# board-v4.net
KiCad netlist of a schematic drawn in EAGLE
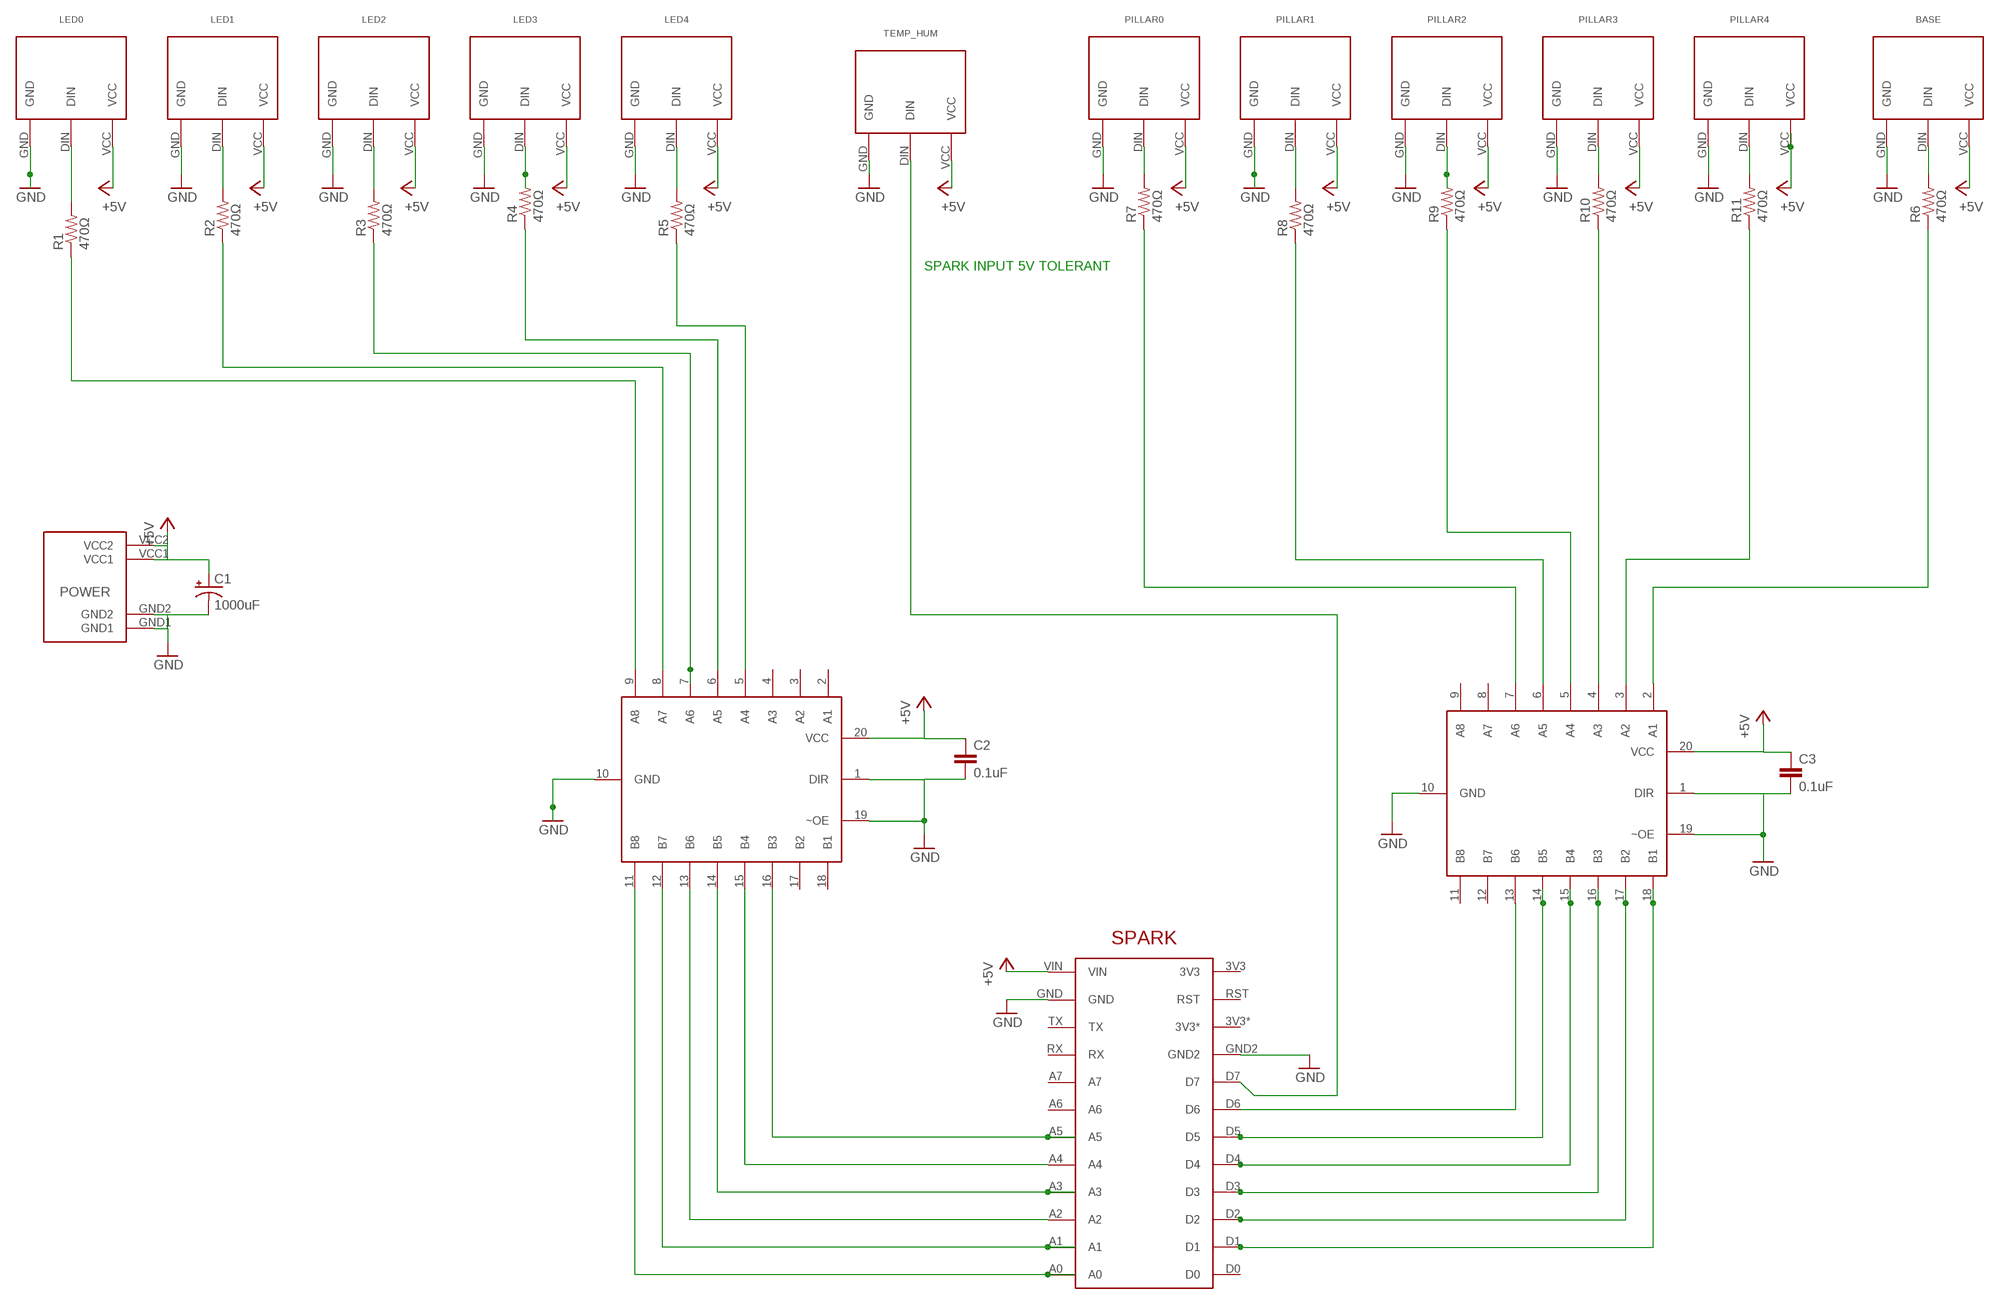
[diagram p0: schematic, sheet 1]

(export (version "E")
  (design (tool "Eeschema 10.0.6"))
  (components
    (comp (ref "BASE")
      (value "MOLEX_3PIN_SMT_43650-310")
      (footprint "eagle-import:MOLEX_3PIN_SMT_43650-310")
      (libsource (lib "eagle-import") (part "MOLEX_3PIN_SMT_43650-310"))
    )
    (comp (ref "C1")
      (value "1000uF")
      (footprint "eagle-import:CPOL-RADIAL-1000UF-25V")
      (libsource (lib "eagle-import") (part "CAP_POLPTH4"))
    )
    (comp (ref "C2")
      (value "0.1uF")
      (footprint "eagle-import:0805")
      (libsource (lib "eagle-import") (part "CAP0805"))
    )
    (comp (ref "C3")
      (value "0.1uF")
      (footprint "eagle-import:0805")
      (libsource (lib "eagle-import") (part "CAP0805"))
    )
    (comp (ref "LED0")
      (value "MOLEX_3PIN_SMT_43650-310")
      (footprint "eagle-import:MOLEX_3PIN_SMT_43650-310")
      (libsource (lib "eagle-import") (part "MOLEX_3PIN_SMT_43650-310"))
    )
    (comp (ref "LED1")
      (value "MOLEX_3PIN_SMT_43650-310")
      (footprint "eagle-import:MOLEX_3PIN_SMT_43650-310")
      (libsource (lib "eagle-import") (part "MOLEX_3PIN_SMT_43650-310"))
    )
    (comp (ref "LED2")
      (value "MOLEX_3PIN_SMT_43650-310")
      (footprint "eagle-import:MOLEX_3PIN_SMT_43650-310")
      (libsource (lib "eagle-import") (part "MOLEX_3PIN_SMT_43650-310"))
    )
    (comp (ref "LED3")
      (value "MOLEX_3PIN_SMT_43650-310")
      (footprint "eagle-import:MOLEX_3PIN_SMT_43650-310")
      (libsource (lib "eagle-import") (part "MOLEX_3PIN_SMT_43650-310"))
    )
    (comp (ref "LED4")
      (value "MOLEX_3PIN_SMT_43650-310")
      (footprint "eagle-import:MOLEX_3PIN_SMT_43650-310")
      (libsource (lib "eagle-import") (part "MOLEX_3PIN_SMT_43650-310"))
    )
    (comp (ref "PILLAR0")
      (value "MOLEX_3PIN_SMT_43650-310")
      (footprint "eagle-import:MOLEX_3PIN_SMT_43650-310")
      (libsource (lib "eagle-import") (part "MOLEX_3PIN_SMT_43650-310"))
    )
    (comp (ref "PILLAR1")
      (value "MOLEX_3PIN_SMT_43650-310")
      (footprint "eagle-import:MOLEX_3PIN_SMT_43650-310")
      (libsource (lib "eagle-import") (part "MOLEX_3PIN_SMT_43650-310"))
    )
    (comp (ref "PILLAR2")
      (value "MOLEX_3PIN_SMT_43650-310")
      (footprint "eagle-import:MOLEX_3PIN_SMT_43650-310")
      (libsource (lib "eagle-import") (part "MOLEX_3PIN_SMT_43650-310"))
    )
    (comp (ref "PILLAR3")
      (value "MOLEX_3PIN_SMT_43650-310")
      (footprint "eagle-import:MOLEX_3PIN_SMT_43650-310")
      (libsource (lib "eagle-import") (part "MOLEX_3PIN_SMT_43650-310"))
    )
    (comp (ref "PILLAR4")
      (value "MOLEX_3PIN_SMT_43650-310")
      (footprint "eagle-import:MOLEX_3PIN_SMT_43650-310")
      (libsource (lib "eagle-import") (part "MOLEX_3PIN_SMT_43650-310"))
    )
    (comp (ref "POWER")
      (value "MOLEX_2PIN_SABRE_POWER")
      (footprint "eagle-import:MOLEX_2PIN_SABRE_POWER")
      (libsource (lib "eagle-import") (part "MOLEX_2PIN_SABRE_POWER"))
    )
    (comp (ref "R1")
      (value "470Ω")
      (footprint "eagle-import:0805")
      (libsource (lib "eagle-import") (part "RESISTOR0805-RES"))
    )
    (comp (ref "R2")
      (value "470Ω")
      (footprint "eagle-import:0805")
      (libsource (lib "eagle-import") (part "RESISTOR0805-RES"))
    )
    (comp (ref "R3")
      (value "470Ω")
      (footprint "eagle-import:0805")
      (libsource (lib "eagle-import") (part "RESISTOR0805-RES"))
    )
    (comp (ref "R4")
      (value "470Ω")
      (footprint "eagle-import:0805")
      (libsource (lib "eagle-import") (part "RESISTOR0805-RES"))
    )
    (comp (ref "R5")
      (value "470Ω")
      (footprint "eagle-import:0805")
      (libsource (lib "eagle-import") (part "RESISTOR0805-RES"))
    )
    (comp (ref "R6")
      (value "470Ω")
      (footprint "eagle-import:0805")
      (libsource (lib "eagle-import") (part "RESISTOR0805-RES"))
    )
    (comp (ref "R7")
      (value "470Ω")
      (footprint "eagle-import:0805")
      (libsource (lib "eagle-import") (part "RESISTOR0805-RES"))
    )
    (comp (ref "R8")
      (value "470Ω")
      (footprint "eagle-import:0805")
      (libsource (lib "eagle-import") (part "RESISTOR0805-RES"))
    )
    (comp (ref "R9")
      (value "470Ω")
      (footprint "eagle-import:0805")
      (libsource (lib "eagle-import") (part "RESISTOR0805-RES"))
    )
    (comp (ref "R10")
      (value "470Ω")
      (footprint "eagle-import:0805")
      (libsource (lib "eagle-import") (part "RESISTOR0805-RES"))
    )
    (comp (ref "R11")
      (value "470Ω")
      (footprint "eagle-import:0805")
      (libsource (lib "eagle-import") (part "RESISTOR0805-RES"))
    )
    (comp (ref "SHIFT1")
      (value "TI_74HCT245DWR")
      (footprint "eagle-import:SOIC-20")
      (libsource (lib "eagle-import") (part "TI_74HCT245DWR"))
    )
    (comp (ref "SHIFT2")
      (value "TI_74HCT245DWR")
      (footprint "eagle-import:SOIC-20")
      (libsource (lib "eagle-import") (part "TI_74HCT245DWR"))
    )
    (comp (ref "SPARK")
      (value "SPARKCORE")
      (footprint "eagle-import:SPARKCORE")
      (libsource (lib "eagle-import") (part "SPARKCORE"))
    )
    (comp (ref "TEMP_HUM")
      (value "MOLEX_3PIN_SMT_43650-310")
      (footprint "eagle-import:MOLEX_3PIN_SMT_43650-310")
      (libsource (lib "eagle-import") (part "MOLEX_3PIN_SMT_43650-310"))
    )
  )
  (nets
    (net (code "1") (name "+5V") (class "Default")
      (node (ref "BASE") (pin "VCC") (pinfunction "VCC_VCC") (pintype "power_in"))
      (node (ref "C1") (pin "1") (pinfunction "+_1") (pintype "passive"))
      (node (ref "C2") (pin "1") (pinfunction "1_1") (pintype "passive"))
      (node (ref "C3") (pin "1") (pinfunction "1_1") (pintype "passive"))
      (node (ref "LED0") (pin "VCC") (pinfunction "VCC_VCC") (pintype "power_in"))
      (node (ref "LED1") (pin "VCC") (pinfunction "VCC_VCC") (pintype "power_in"))
      (node (ref "LED2") (pin "VCC") (pinfunction "VCC_VCC") (pintype "power_in"))
      (node (ref "LED3") (pin "VCC") (pinfunction "VCC_VCC") (pintype "power_in"))
      (node (ref "LED4") (pin "VCC") (pinfunction "VCC_VCC") (pintype "power_in"))
      (node (ref "PILLAR0") (pin "VCC") (pinfunction "VCC_VCC") (pintype "power_in"))
      (node (ref "PILLAR1") (pin "VCC") (pinfunction "VCC_VCC") (pintype "power_in"))
      (node (ref "PILLAR2") (pin "VCC") (pinfunction "VCC_VCC") (pintype "power_in"))
      (node (ref "PILLAR3") (pin "VCC") (pinfunction "VCC_VCC") (pintype "power_in"))
      (node (ref "PILLAR4") (pin "VCC") (pinfunction "VCC_VCC") (pintype "power_in"))
      (node (ref "POWER") (pin "VCC1") (pinfunction "VCC1_VCC1") (pintype "bidirectional"))
      (node (ref "POWER") (pin "VCC2") (pinfunction "VCC2_VCC2") (pintype "power_in"))
      (node (ref "SHIFT1") (pin "20") (pinfunction "VCC_20") (pintype "bidirectional"))
      (node (ref "SHIFT2") (pin "20") (pinfunction "VCC_20") (pintype "bidirectional"))
      (node (ref "SPARK") (pin "VIN") (pinfunction "VIN_VIN") (pintype "power_in"))
      (node (ref "TEMP_HUM") (pin "VCC") (pinfunction "VCC_VCC") (pintype "power_in"))
    )
    (net (code "2") (name "GND") (class "Default")
      (node (ref "BASE") (pin "GND") (pinfunction "GND_GND") (pintype "power_in"))
      (node (ref "C1") (pin "2") (pinfunction "-_2") (pintype "passive"))
      (node (ref "C2") (pin "2") (pinfunction "2_2") (pintype "passive"))
      (node (ref "C3") (pin "2") (pinfunction "2_2") (pintype "passive"))
      (node (ref "LED0") (pin "GND") (pinfunction "GND_GND") (pintype "power_in"))
      (node (ref "LED1") (pin "GND") (pinfunction "GND_GND") (pintype "power_in"))
      (node (ref "LED2") (pin "GND") (pinfunction "GND_GND") (pintype "power_in"))
      (node (ref "LED3") (pin "GND") (pinfunction "GND_GND") (pintype "power_in"))
      (node (ref "LED4") (pin "GND") (pinfunction "GND_GND") (pintype "power_in"))
      (node (ref "PILLAR0") (pin "GND") (pinfunction "GND_GND") (pintype "power_in"))
      (node (ref "PILLAR1") (pin "GND") (pinfunction "GND_GND") (pintype "power_in"))
      (node (ref "PILLAR2") (pin "GND") (pinfunction "GND_GND") (pintype "power_in"))
      (node (ref "PILLAR3") (pin "GND") (pinfunction "GND_GND") (pintype "power_in"))
      (node (ref "PILLAR4") (pin "GND") (pinfunction "GND_GND") (pintype "power_in"))
      (node (ref "POWER") (pin "GND1") (pinfunction "GND1_GND1") (pintype "power_in"))
      (node (ref "POWER") (pin "GND2") (pinfunction "GND2_GND2") (pintype "bidirectional"))
      (node (ref "SHIFT1") (pin "1") (pinfunction "DIR_1") (pintype "bidirectional"))
      (node (ref "SHIFT1") (pin "10") (pinfunction "GND_10") (pintype "bidirectional"))
      (node (ref "SHIFT1") (pin "19") (pinfunction "~{OE}_19") (pintype "bidirectional"))
      (node (ref "SHIFT2") (pin "1") (pinfunction "DIR_1") (pintype "bidirectional"))
      (node (ref "SHIFT2") (pin "10") (pinfunction "GND_10") (pintype "bidirectional"))
      (node (ref "SHIFT2") (pin "19") (pinfunction "~{OE}_19") (pintype "bidirectional"))
      (node (ref "SPARK") (pin "GND") (pinfunction "GND_GND") (pintype "power_in"))
      (node (ref "SPARK") (pin "GND2") (pinfunction "GND2_GND2") (pintype "bidirectional"))
      (node (ref "TEMP_HUM") (pin "GND") (pinfunction "GND_GND") (pintype "power_in"))
    )
    (net (code "3") (name "Net-(BASE-PadDIN)") (class "Default")
      (node (ref "BASE") (pin "DIN") (pinfunction "DIN_DIN") (pintype "bidirectional"))
      (node (ref "R6") (pin "2") (pinfunction "2_2") (pintype "passive"))
    )
    (net (code "4") (name "Net-(LED0-PadDIN)") (class "Default")
      (node (ref "LED0") (pin "DIN") (pinfunction "DIN_DIN") (pintype "bidirectional"))
      (node (ref "R1") (pin "2") (pinfunction "2_2") (pintype "passive"))
    )
    (net (code "5") (name "Net-(LED1-PadDIN)") (class "Default")
      (node (ref "LED1") (pin "DIN") (pinfunction "DIN_DIN") (pintype "bidirectional"))
      (node (ref "R2") (pin "2") (pinfunction "2_2") (pintype "passive"))
    )
    (net (code "6") (name "Net-(LED2-PadDIN)") (class "Default")
      (node (ref "LED2") (pin "DIN") (pinfunction "DIN_DIN") (pintype "bidirectional"))
      (node (ref "R3") (pin "2") (pinfunction "2_2") (pintype "passive"))
    )
    (net (code "7") (name "Net-(LED3-PadDIN)") (class "Default")
      (node (ref "LED3") (pin "DIN") (pinfunction "DIN_DIN") (pintype "bidirectional"))
      (node (ref "R4") (pin "2") (pinfunction "2_2") (pintype "passive"))
    )
    (net (code "8") (name "Net-(LED4-PadDIN)") (class "Default")
      (node (ref "LED4") (pin "DIN") (pinfunction "DIN_DIN") (pintype "bidirectional"))
      (node (ref "R5") (pin "2") (pinfunction "2_2") (pintype "passive"))
    )
    (net (code "9") (name "Net-(PILLAR0-PadDIN)") (class "Default")
      (node (ref "PILLAR0") (pin "DIN") (pinfunction "DIN_DIN") (pintype "bidirectional"))
      (node (ref "R7") (pin "2") (pinfunction "2_2") (pintype "passive"))
    )
    (net (code "10") (name "Net-(PILLAR1-PadDIN)") (class "Default")
      (node (ref "PILLAR1") (pin "DIN") (pinfunction "DIN_DIN") (pintype "bidirectional"))
      (node (ref "R8") (pin "2") (pinfunction "2_2") (pintype "passive"))
    )
    (net (code "11") (name "Net-(PILLAR2-PadDIN)") (class "Default")
      (node (ref "PILLAR2") (pin "DIN") (pinfunction "DIN_DIN") (pintype "bidirectional"))
      (node (ref "R9") (pin "2") (pinfunction "2_2") (pintype "passive"))
    )
    (net (code "12") (name "Net-(PILLAR3-PadDIN)") (class "Default")
      (node (ref "PILLAR3") (pin "DIN") (pinfunction "DIN_DIN") (pintype "bidirectional"))
      (node (ref "R10") (pin "2") (pinfunction "2_2") (pintype "passive"))
    )
    (net (code "13") (name "Net-(PILLAR4-PadDIN)") (class "Default")
      (node (ref "PILLAR4") (pin "DIN") (pinfunction "DIN_DIN") (pintype "bidirectional"))
      (node (ref "R11") (pin "2") (pinfunction "2_2") (pintype "passive"))
    )
    (net (code "14") (name "Net-(SHIFT1-A4)") (class "Default")
      (node (ref "R5") (pin "1") (pinfunction "1_1") (pintype "passive"))
      (node (ref "SHIFT1") (pin "5") (pinfunction "A4_5") (pintype "bidirectional"))
    )
    (net (code "15") (name "Net-(SHIFT1-A5)") (class "Default")
      (node (ref "R4") (pin "1") (pinfunction "1_1") (pintype "passive"))
      (node (ref "SHIFT1") (pin "6") (pinfunction "A5_6") (pintype "bidirectional"))
    )
    (net (code "16") (name "Net-(SHIFT1-A6)") (class "Default")
      (node (ref "R3") (pin "1") (pinfunction "1_1") (pintype "passive"))
      (node (ref "SHIFT1") (pin "7") (pinfunction "A6_7") (pintype "bidirectional"))
    )
    (net (code "17") (name "Net-(SHIFT1-A7)") (class "Default")
      (node (ref "R2") (pin "1") (pinfunction "1_1") (pintype "passive"))
      (node (ref "SHIFT1") (pin "8") (pinfunction "A7_8") (pintype "bidirectional"))
    )
    (net (code "18") (name "Net-(SHIFT1-A8)") (class "Default")
      (node (ref "R1") (pin "1") (pinfunction "1_1") (pintype "passive"))
      (node (ref "SHIFT1") (pin "9") (pinfunction "A8_9") (pintype "bidirectional"))
    )
    (net (code "19") (name "Net-(SHIFT1-B3)") (class "Default")
      (node (ref "SHIFT1") (pin "16") (pinfunction "B3_16") (pintype "bidirectional"))
      (node (ref "SPARK") (pin "A5") (pinfunction "A5_A5") (pintype "bidirectional"))
    )
    (net (code "20") (name "Net-(SHIFT1-B4)") (class "Default")
      (node (ref "SHIFT1") (pin "15") (pinfunction "B4_15") (pintype "bidirectional"))
      (node (ref "SPARK") (pin "A4") (pinfunction "A4_A4") (pintype "bidirectional"))
    )
    (net (code "21") (name "Net-(SHIFT1-B5)") (class "Default")
      (node (ref "SHIFT1") (pin "14") (pinfunction "B5_14") (pintype "bidirectional"))
      (node (ref "SPARK") (pin "A3") (pinfunction "A3_A3") (pintype "bidirectional"))
    )
    (net (code "22") (name "Net-(SHIFT1-B6)") (class "Default")
      (node (ref "SHIFT1") (pin "13") (pinfunction "B6_13") (pintype "bidirectional"))
      (node (ref "SPARK") (pin "A2") (pinfunction "A2_A2") (pintype "bidirectional"))
    )
    (net (code "23") (name "Net-(SHIFT1-B7)") (class "Default")
      (node (ref "SHIFT1") (pin "12") (pinfunction "B7_12") (pintype "bidirectional"))
      (node (ref "SPARK") (pin "A1") (pinfunction "A1_A1") (pintype "bidirectional"))
    )
    (net (code "24") (name "Net-(SHIFT1-B8)") (class "Default")
      (node (ref "SHIFT1") (pin "11") (pinfunction "B8_11") (pintype "bidirectional"))
      (node (ref "SPARK") (pin "A0") (pinfunction "A0_A0") (pintype "bidirectional"))
    )
    (net (code "25") (name "Net-(SHIFT2-A1)") (class "Default")
      (node (ref "R6") (pin "1") (pinfunction "1_1") (pintype "passive"))
      (node (ref "SHIFT2") (pin "2") (pinfunction "A1_2") (pintype "bidirectional"))
    )
    (net (code "26") (name "Net-(SHIFT2-A2)") (class "Default")
      (node (ref "R11") (pin "1") (pinfunction "1_1") (pintype "passive"))
      (node (ref "SHIFT2") (pin "3") (pinfunction "A2_3") (pintype "bidirectional"))
    )
    (net (code "27") (name "Net-(SHIFT2-A3)") (class "Default")
      (node (ref "R10") (pin "1") (pinfunction "1_1") (pintype "passive"))
      (node (ref "SHIFT2") (pin "4") (pinfunction "A3_4") (pintype "bidirectional"))
    )
    (net (code "28") (name "Net-(SHIFT2-A4)") (class "Default")
      (node (ref "R9") (pin "1") (pinfunction "1_1") (pintype "passive"))
      (node (ref "SHIFT2") (pin "5") (pinfunction "A4_5") (pintype "bidirectional"))
    )
    (net (code "29") (name "Net-(SHIFT2-A5)") (class "Default")
      (node (ref "R8") (pin "1") (pinfunction "1_1") (pintype "passive"))
      (node (ref "SHIFT2") (pin "6") (pinfunction "A5_6") (pintype "bidirectional"))
    )
    (net (code "30") (name "Net-(SHIFT2-A6)") (class "Default")
      (node (ref "R7") (pin "1") (pinfunction "1_1") (pintype "passive"))
      (node (ref "SHIFT2") (pin "7") (pinfunction "A6_7") (pintype "bidirectional"))
    )
    (net (code "31") (name "Net-(SHIFT2-B1)") (class "Default")
      (node (ref "SHIFT2") (pin "18") (pinfunction "B1_18") (pintype "bidirectional"))
      (node (ref "SPARK") (pin "D1") (pinfunction "D1_D1") (pintype "bidirectional"))
    )
    (net (code "32") (name "Net-(SHIFT2-B2)") (class "Default")
      (node (ref "SHIFT2") (pin "17") (pinfunction "B2_17") (pintype "bidirectional"))
      (node (ref "SPARK") (pin "D2") (pinfunction "D2_D2") (pintype "bidirectional"))
    )
    (net (code "33") (name "Net-(SHIFT2-B3)") (class "Default")
      (node (ref "SHIFT2") (pin "16") (pinfunction "B3_16") (pintype "bidirectional"))
      (node (ref "SPARK") (pin "D3") (pinfunction "D3_D3") (pintype "bidirectional"))
    )
    (net (code "34") (name "Net-(SHIFT2-B4)") (class "Default")
      (node (ref "SHIFT2") (pin "15") (pinfunction "B4_15") (pintype "bidirectional"))
      (node (ref "SPARK") (pin "D4") (pinfunction "D4_D4") (pintype "bidirectional"))
    )
    (net (code "35") (name "Net-(SHIFT2-B5)") (class "Default")
      (node (ref "SHIFT2") (pin "14") (pinfunction "B5_14") (pintype "bidirectional"))
      (node (ref "SPARK") (pin "D5") (pinfunction "D5_D5") (pintype "bidirectional"))
    )
    (net (code "36") (name "Net-(SHIFT2-B6)") (class "Default")
      (node (ref "SHIFT2") (pin "13") (pinfunction "B6_13") (pintype "bidirectional"))
      (node (ref "SPARK") (pin "D6") (pinfunction "D6_D6") (pintype "bidirectional"))
    )
    (net (code "37") (name "Net-(SPARK-PadD7)") (class "Default")
      (node (ref "SPARK") (pin "D7") (pinfunction "D7_D7") (pintype "bidirectional"))
      (node (ref "TEMP_HUM") (pin "DIN") (pinfunction "DIN_DIN") (pintype "bidirectional"))
    )
    (net (code "38") (name "unconnected-(SHIFT1-A1-Pad2)") (class "Default")
      (node (ref "SHIFT1") (pin "2") (pinfunction "A1_2") (pintype "bidirectional"))
    )
    (net (code "39") (name "unconnected-(SHIFT1-A2-Pad3)") (class "Default")
      (node (ref "SHIFT1") (pin "3") (pinfunction "A2_3") (pintype "bidirectional"))
    )
    (net (code "40") (name "unconnected-(SHIFT1-A3-Pad4)") (class "Default")
      (node (ref "SHIFT1") (pin "4") (pinfunction "A3_4") (pintype "bidirectional"))
    )
    (net (code "41") (name "unconnected-(SHIFT1-B1-Pad18)") (class "Default")
      (node (ref "SHIFT1") (pin "18") (pinfunction "B1_18") (pintype "bidirectional"))
    )
    (net (code "42") (name "unconnected-(SHIFT1-B2-Pad17)") (class "Default")
      (node (ref "SHIFT1") (pin "17") (pinfunction "B2_17") (pintype "bidirectional"))
    )
    (net (code "43") (name "unconnected-(SHIFT2-A7-Pad8)") (class "Default")
      (node (ref "SHIFT2") (pin "8") (pinfunction "A7_8") (pintype "bidirectional"))
    )
    (net (code "44") (name "unconnected-(SHIFT2-A8-Pad9)") (class "Default")
      (node (ref "SHIFT2") (pin "9") (pinfunction "A8_9") (pintype "bidirectional"))
    )
    (net (code "45") (name "unconnected-(SHIFT2-B7-Pad12)") (class "Default")
      (node (ref "SHIFT2") (pin "12") (pinfunction "B7_12") (pintype "bidirectional"))
    )
    (net (code "46") (name "unconnected-(SHIFT2-B8-Pad11)") (class "Default")
      (node (ref "SHIFT2") (pin "11") (pinfunction "B8_11") (pintype "bidirectional"))
    )
    (net (code "47") (name "unconnected-(SPARK-Pad3V3)") (class "Default")
      (node (ref "SPARK") (pin "3V3") (pinfunction "3V3_3V3") (pintype "bidirectional"))
    )
    (net (code "48") (name "unconnected-(SPARK-Pad3V3*)") (class "Default")
      (node (ref "SPARK") (pin "3V3*") (pinfunction "3V3*_3V3*") (pintype "bidirectional"))
    )
    (net (code "49") (name "unconnected-(SPARK-PadA6)") (class "Default")
      (node (ref "SPARK") (pin "A6") (pinfunction "A6_A6") (pintype "bidirectional"))
    )
    (net (code "50") (name "unconnected-(SPARK-PadA7)") (class "Default")
      (node (ref "SPARK") (pin "A7") (pinfunction "A7_A7") (pintype "bidirectional"))
    )
    (net (code "51") (name "unconnected-(SPARK-PadD0)") (class "Default")
      (node (ref "SPARK") (pin "D0") (pinfunction "D0_D0") (pintype "bidirectional"))
    )
    (net (code "52") (name "unconnected-(SPARK-PadRST)") (class "Default")
      (node (ref "SPARK") (pin "RST") (pinfunction "RST_RST") (pintype "bidirectional"))
    )
    (net (code "53") (name "unconnected-(SPARK-PadRX)") (class "Default")
      (node (ref "SPARK") (pin "RX") (pinfunction "RX_RX") (pintype "bidirectional"))
    )
    (net (code "54") (name "unconnected-(SPARK-PadTX)") (class "Default")
      (node (ref "SPARK") (pin "TX") (pinfunction "TX_TX") (pintype "bidirectional"))
    )
  )
)
